# AMC.net
KiCad netlist of a schematic drawn in Altium Designer
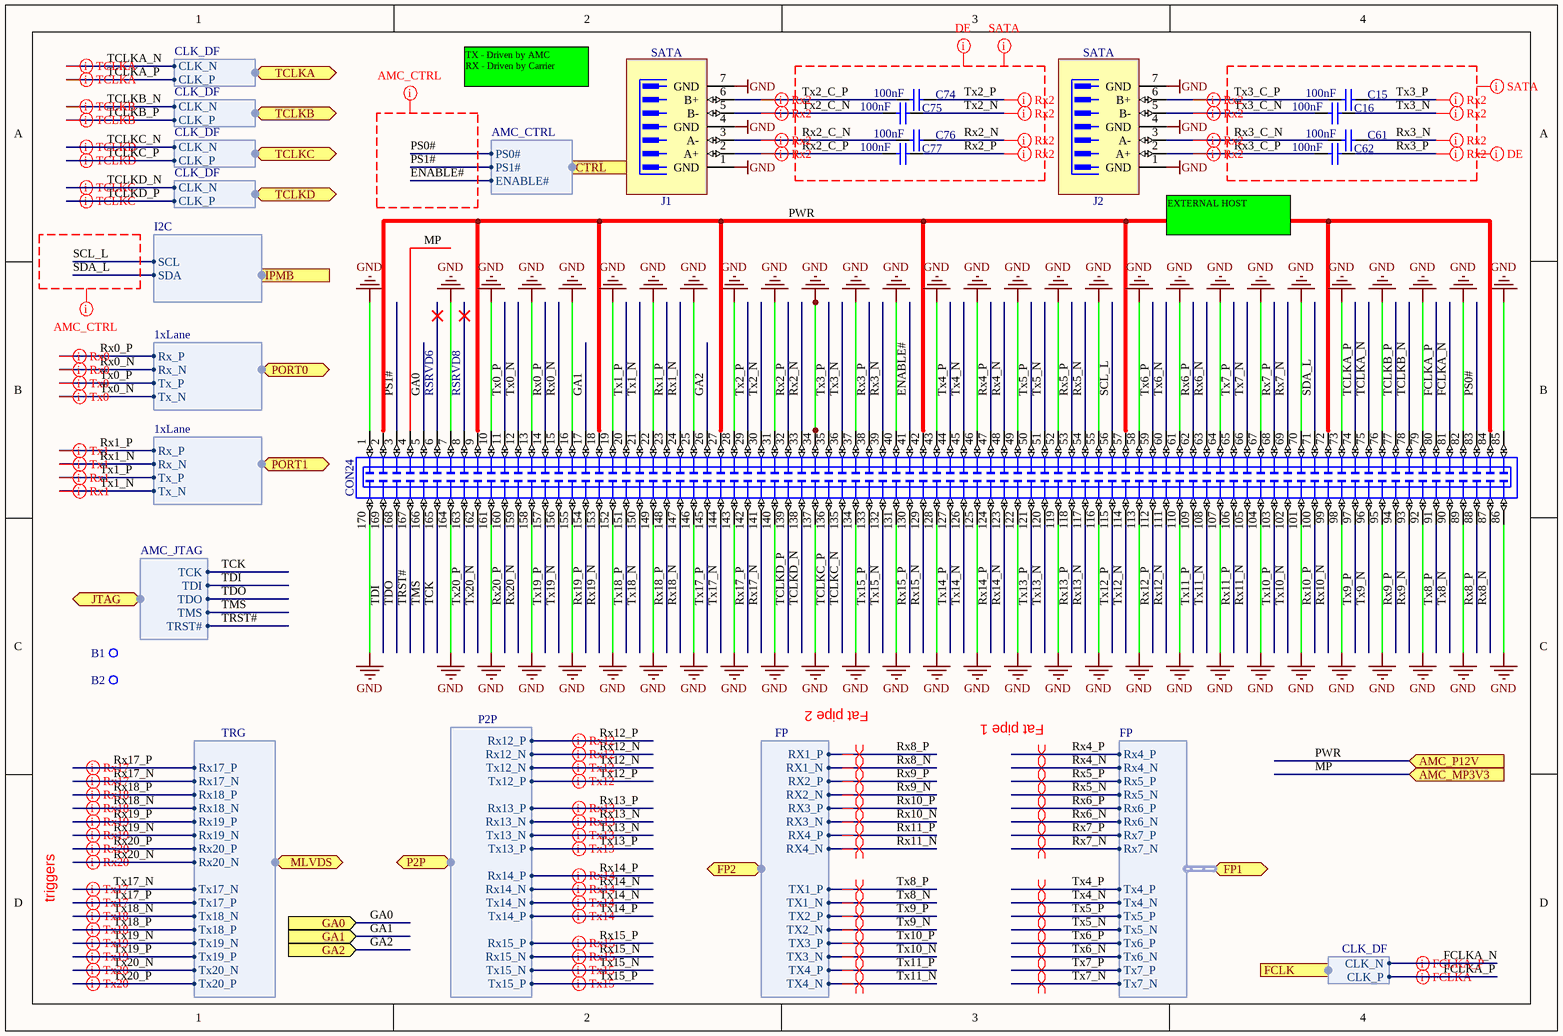
[diagram p0: AMC.SchDoc]

(export (version "E")
  (design (tool "Eeschema 10.0.6"))
  (components
    (comp (ref "B1")
      (value "Plated Hole")
      (footprint "MTG320_550")
      (description "Single Terminal Socket")
      (fields (field (name "PART NUMBER") "PLATED_HOLE3.2_PAD5.5") (field (name "AUTHOR") "CERN DEM JMW"))
      (libsource (lib "Eletro-mechanical") (part "Single Terminal Socket"))
    )
    (comp (ref "B2")
      (value "Plated Hole")
      (footprint "MTG320_550")
      (description "Single Terminal Socket")
      (fields (field (name "PART NUMBER") "PLATED_HOLE3.2_PAD5.5") (field (name "AUTHOR") "CERN DEM JMW"))
      (libsource (lib "Eletro-mechanical") (part "Single Terminal Socket"))
    )
    (comp (ref "C15")
      (value "100nF")
      (footprint "CAPC0603X33N")
      (description "Non-polarised capacitor")
      (fields
        (field (name "PART NUMBER") "CC0201_100NF_6.3V_10%_X5R")
        (field (name "VOLTAGE") "6.3V")
        (field (name "AUTHOR") "CERN DEM JLC")
      )
      (libsource (lib "Capacitors") (part "Capacitor - non polarized"))
    )
    (comp (ref "C16")
      (value "100nF")
      (footprint "CAPC0603X33N")
      (description "Non-polarised capacitor")
      (fields
        (field (name "PART NUMBER") "CC0201_100NF_6.3V_10%_X5R")
        (field (name "VOLTAGE") "6.3V")
        (field (name "AUTHOR") "CERN DEM JLC")
      )
      (libsource (lib "Capacitors") (part "Capacitor - non polarized"))
    )
    (comp (ref "C61")
      (value "100nF")
      (footprint "CAPC0603X33N")
      (description "Non-polarised capacitor")
      (fields
        (field (name "PART NUMBER") "CC0201_100NF_6.3V_10%_X5R")
        (field (name "VOLTAGE") "6.3V")
        (field (name "AUTHOR") "CERN DEM JLC")
      )
      (libsource (lib "Capacitors") (part "Capacitor - non polarized"))
    )
    (comp (ref "C62")
      (value "100nF")
      (footprint "CAPC0603X33N")
      (description "Non-polarised capacitor")
      (fields
        (field (name "PART NUMBER") "CC0201_100NF_6.3V_10%_X5R")
        (field (name "VOLTAGE") "6.3V")
        (field (name "AUTHOR") "CERN DEM JLC")
      )
      (libsource (lib "Capacitors") (part "Capacitor - non polarized"))
    )
    (comp (ref "C74")
      (value "100nF")
      (footprint "CAPC0603X33N")
      (description "Non-polarised capacitor")
      (fields
        (field (name "PART NUMBER") "CC0201_100NF_6.3V_10%_X5R")
        (field (name "VOLTAGE") "6.3V")
        (field (name "AUTHOR") "CERN DEM JLC")
      )
      (libsource (lib "Capacitors") (part "Capacitor - non polarized"))
    )
    (comp (ref "C75")
      (value "100nF")
      (footprint "CAPC0603X33N")
      (description "Non-polarised capacitor")
      (fields
        (field (name "PART NUMBER") "CC0201_100NF_6.3V_10%_X5R")
        (field (name "VOLTAGE") "6.3V")
        (field (name "AUTHOR") "CERN DEM JLC")
      )
      (libsource (lib "Capacitors") (part "Capacitor - non polarized"))
    )
    (comp (ref "C76")
      (value "100nF")
      (footprint "CAPC0603X33N")
      (description "Non-polarised capacitor")
      (fields
        (field (name "PART NUMBER") "CC0201_100NF_6.3V_10%_X5R")
        (field (name "VOLTAGE") "6.3V")
        (field (name "AUTHOR") "CERN DEM JLC")
      )
      (libsource (lib "Capacitors") (part "Capacitor - non polarized"))
    )
    (comp (ref "C77")
      (value "100nF")
      (footprint "CAPC0603X33N")
      (description "Non-polarised capacitor")
      (fields
        (field (name "PART NUMBER") "CC0201_100NF_6.3V_10%_X5R")
        (field (name "VOLTAGE") "6.3V")
        (field (name "AUTHOR") "CERN DEM JLC")
      )
      (libsource (lib "Capacitors") (part "Capacitor - non polarized"))
    )
    (comp (ref "CON24")
      (value "SAMTEC_MTCA-085-02-S-DV-SMT-K-TR")
      (footprint "SAMTEC_MTCA-085-02-S-DV-SMT-K-TR")
      (description "170 Poles,  Micro TCA (Telecom Computing Architecture) Edge Card Socket")
      (fields
        (field (name "MANUFACTURER") "SAMTEC")
        (field (name "MANUFACTURER PART NUMBER") "MTCA-085-02-S-DV-SMT-K-TR")
        (field (name "AUTHOR") "CERN DEM JLC")
      )
      (libsource (lib "Connectors") (part "Micro TCA Female 170"))
    )
    (comp (ref "J1")
      (value "SATA")
      (footprint "MOLEX_67800-5005")
      (description "7 Pin SATA Receptacle")
      (fields
        (field (name "PART NUMBER") "MOLEX_67800-5005")
        (field (name "MANUFACTURER") "MOLEX")
        (field (name "AUTHOR") "CERN DEM MR")
      )
      (libsource (lib "Connectors") (part "Connector SATA 7 Male"))
    )
    (comp (ref "J2")
      (value "SATA")
      (footprint "MOLEX_67800-5005")
      (description "7 Pin SATA Receptacle")
      (fields
        (field (name "PART NUMBER") "MOLEX_67800-5005")
        (field (name "MANUFACTURER") "MOLEX")
        (field (name "AUTHOR") "CERN DEM MR")
      )
      (libsource (lib "Connectors") (part "Connector SATA 7 Male"))
    )
  )
  (nets
    (net (code "9") (name "/ENABLE#") (class "Default")
      (node (ref "CON24") (pin "41") (pinfunction "41_41") (pintype "bidirectional"))
    )
    (net (code "10") (name "/FCLKA_N") (class "Default")
      (node (ref "CON24") (pin "81") (pinfunction "81_81") (pintype "bidirectional"))
    )
    (net (code "11") (name "/FCLKA_P") (class "Default")
      (node (ref "CON24") (pin "80") (pinfunction "80_80") (pintype "bidirectional"))
    )
    (net (code "12") (name "/GA0") (class "Default")
      (node (ref "CON24") (pin "5") (pinfunction "5_5") (pintype "bidirectional"))
    )
    (net (code "13") (name "/GA1") (class "Default")
      (node (ref "CON24") (pin "17") (pinfunction "17_17") (pintype "bidirectional"))
    )
    (net (code "14") (name "/GA2") (class "Default")
      (node (ref "CON24") (pin "26") (pinfunction "26_26") (pintype "bidirectional"))
    )
    (net (code "15") (name "/MP") (class "Default")
      (node (ref "CON24") (pin "4") (pinfunction "4_4") (pintype "bidirectional"))
    )
    (net (code "16") (name "/PS0#") (class "Default")
      (node (ref "CON24") (pin "83") (pinfunction "83_83") (pintype "bidirectional"))
    )
    (net (code "17") (name "/PS1#") (class "Default")
      (node (ref "CON24") (pin "3") (pinfunction "3_3") (pintype "bidirectional"))
    )
    (net (code "18") (name "/PWR") (class "Default")
      (node (ref "CON24") (pin "18") (pinfunction "18_18") (pintype "bidirectional"))
      (node (ref "CON24") (pin "2") (pinfunction "2_2") (pintype "bidirectional"))
      (node (ref "CON24") (pin "27") (pinfunction "27_27") (pintype "bidirectional"))
      (node (ref "CON24") (pin "42") (pinfunction "42_42") (pintype "bidirectional"))
      (node (ref "CON24") (pin "57") (pinfunction "57_57") (pintype "bidirectional"))
      (node (ref "CON24") (pin "72") (pinfunction "72_72") (pintype "bidirectional"))
      (node (ref "CON24") (pin "84") (pinfunction "84_84") (pintype "bidirectional"))
      (node (ref "CON24") (pin "9") (pinfunction "9_9") (pintype "bidirectional"))
    )
    (net (code "19") (name "/Rx0_N") (class "Default")
      (node (ref "CON24") (pin "15") (pinfunction "15_15") (pintype "bidirectional"))
    )
    (net (code "20") (name "/Rx0_P") (class "Default")
      (node (ref "CON24") (pin "14") (pinfunction "14_14") (pintype "bidirectional"))
    )
    (net (code "21") (name "/Rx1_N") (class "Default")
      (node (ref "CON24") (pin "24") (pinfunction "24_24") (pintype "bidirectional"))
    )
    (net (code "22") (name "/Rx1_P") (class "Default")
      (node (ref "CON24") (pin "23") (pinfunction "23_23") (pintype "bidirectional"))
    )
    (net (code "23") (name "/Rx2_C_N") (class "Default")
      (node (ref "C76") (pin "1") (pinfunction "1_1") (pintype "passive"))
      (node (ref "J1") (pin "3") (pinfunction "A-_3") (pintype "bidirectional"))
    )
    (net (code "24") (name "/Rx2_C_P") (class "Default")
      (node (ref "C77") (pin "1") (pinfunction "1_1") (pintype "passive"))
      (node (ref "J1") (pin "2") (pinfunction "A+_2") (pintype "bidirectional"))
    )
    (net (code "25") (name "/Rx2_N") (class "Default")
      (node (ref "C76") (pin "2") (pinfunction "2_2") (pintype "passive"))
      (node (ref "CON24") (pin "33") (pinfunction "33_33") (pintype "bidirectional"))
    )
    (net (code "26") (name "/Rx2_P") (class "Default")
      (node (ref "C77") (pin "2") (pinfunction "2_2") (pintype "passive"))
      (node (ref "CON24") (pin "32") (pinfunction "32_32") (pintype "bidirectional"))
    )
    (net (code "27") (name "/Rx3_C_N") (class "Default")
      (node (ref "C61") (pin "1") (pinfunction "1_1") (pintype "passive"))
      (node (ref "J2") (pin "3") (pinfunction "A-_3") (pintype "bidirectional"))
    )
    (net (code "28") (name "/Rx3_C_P") (class "Default")
      (node (ref "C62") (pin "1") (pinfunction "1_1") (pintype "passive"))
      (node (ref "J2") (pin "2") (pinfunction "A+_2") (pintype "bidirectional"))
    )
    (net (code "29") (name "/Rx3_N") (class "Default")
      (node (ref "C61") (pin "2") (pinfunction "2_2") (pintype "passive"))
      (node (ref "CON24") (pin "39") (pinfunction "39_39") (pintype "bidirectional"))
    )
    (net (code "30") (name "/Rx3_P") (class "Default")
      (node (ref "C62") (pin "2") (pinfunction "2_2") (pintype "passive"))
      (node (ref "CON24") (pin "38") (pinfunction "38_38") (pintype "bidirectional"))
    )
    (net (code "31") (name "/Rx4_N") (class "Default")
      (node (ref "CON24") (pin "48") (pinfunction "48_48") (pintype "bidirectional"))
    )
    (net (code "32") (name "/Rx4_P") (class "Default")
      (node (ref "CON24") (pin "47") (pinfunction "47_47") (pintype "bidirectional"))
    )
    (net (code "33") (name "/Rx5_N") (class "Default")
      (node (ref "CON24") (pin "54") (pinfunction "54_54") (pintype "bidirectional"))
    )
    (net (code "34") (name "/Rx5_P") (class "Default")
      (node (ref "CON24") (pin "53") (pinfunction "53_53") (pintype "bidirectional"))
    )
    (net (code "35") (name "/Rx6_N") (class "Default")
      (node (ref "CON24") (pin "63") (pinfunction "63_63") (pintype "bidirectional"))
    )
    (net (code "36") (name "/Rx6_P") (class "Default")
      (node (ref "CON24") (pin "62") (pinfunction "62_62") (pintype "bidirectional"))
    )
    (net (code "37") (name "/Rx7_N") (class "Default")
      (node (ref "CON24") (pin "69") (pinfunction "69_69") (pintype "bidirectional"))
    )
    (net (code "38") (name "/Rx7_P") (class "Default")
      (node (ref "CON24") (pin "68") (pinfunction "68_68") (pintype "bidirectional"))
    )
    (net (code "39") (name "/Rx8_N") (class "Default")
      (node (ref "CON24") (pin "87") (pinfunction "87_87") (pintype "bidirectional"))
    )
    (net (code "40") (name "/Rx8_P") (class "Default")
      (node (ref "CON24") (pin "88") (pinfunction "88_88") (pintype "bidirectional"))
    )
    (net (code "41") (name "/Rx9_N") (class "Default")
      (node (ref "CON24") (pin "93") (pinfunction "93_93") (pintype "bidirectional"))
    )
    (net (code "42") (name "/Rx9_P") (class "Default")
      (node (ref "CON24") (pin "94") (pinfunction "94_94") (pintype "bidirectional"))
    )
    (net (code "43") (name "/Rx10_N") (class "Default")
      (node (ref "CON24") (pin "99") (pinfunction "99_99") (pintype "bidirectional"))
    )
    (net (code "44") (name "/Rx10_P") (class "Default")
      (node (ref "CON24") (pin "100") (pinfunction "100_100") (pintype "bidirectional"))
    )
    (net (code "45") (name "/Rx11_N") (class "Default")
      (node (ref "CON24") (pin "105") (pinfunction "105_105") (pintype "bidirectional"))
    )
    (net (code "46") (name "/Rx11_P") (class "Default")
      (node (ref "CON24") (pin "106") (pinfunction "106_106") (pintype "bidirectional"))
    )
    (net (code "47") (name "/Rx12_N") (class "Default")
      (node (ref "CON24") (pin "111") (pinfunction "111_111") (pintype "bidirectional"))
    )
    (net (code "48") (name "/Rx12_P") (class "Default")
      (node (ref "CON24") (pin "112") (pinfunction "112_112") (pintype "bidirectional"))
    )
    (net (code "49") (name "/Rx13_N") (class "Default")
      (node (ref "CON24") (pin "117") (pinfunction "117_117") (pintype "bidirectional"))
    )
    (net (code "50") (name "/Rx13_P") (class "Default")
      (node (ref "CON24") (pin "118") (pinfunction "118_118") (pintype "bidirectional"))
    )
    (net (code "51") (name "/Rx14_N") (class "Default")
      (node (ref "CON24") (pin "123") (pinfunction "123_123") (pintype "bidirectional"))
    )
    (net (code "52") (name "/Rx14_P") (class "Default")
      (node (ref "CON24") (pin "124") (pinfunction "124_124") (pintype "bidirectional"))
    )
    (net (code "53") (name "/Rx15_N") (class "Default")
      (node (ref "CON24") (pin "129") (pinfunction "129_129") (pintype "bidirectional"))
    )
    (net (code "54") (name "/Rx15_P") (class "Default")
      (node (ref "CON24") (pin "130") (pinfunction "130_130") (pintype "bidirectional"))
    )
    (net (code "55") (name "/Rx17_N") (class "Default")
      (node (ref "CON24") (pin "141") (pinfunction "141_141") (pintype "bidirectional"))
    )
    (net (code "56") (name "/Rx17_P") (class "Default")
      (node (ref "CON24") (pin "142") (pinfunction "142_142") (pintype "bidirectional"))
    )
    (net (code "57") (name "/Rx18_N") (class "Default")
      (node (ref "CON24") (pin "147") (pinfunction "147_147") (pintype "bidirectional"))
    )
    (net (code "58") (name "/Rx18_P") (class "Default")
      (node (ref "CON24") (pin "148") (pinfunction "148_148") (pintype "bidirectional"))
    )
    (net (code "59") (name "/Rx19_N") (class "Default")
      (node (ref "CON24") (pin "153") (pinfunction "153_153") (pintype "bidirectional"))
    )
    (net (code "60") (name "/Rx19_P") (class "Default")
      (node (ref "CON24") (pin "154") (pinfunction "154_154") (pintype "bidirectional"))
    )
    (net (code "61") (name "/Rx20_N") (class "Default")
      (node (ref "CON24") (pin "159") (pinfunction "159_159") (pintype "bidirectional"))
    )
    (net (code "62") (name "/Rx20_P") (class "Default")
      (node (ref "CON24") (pin "160") (pinfunction "160_160") (pintype "bidirectional"))
    )
    (net (code "63") (name "/SCL_L") (class "Default")
      (node (ref "CON24") (pin "56") (pinfunction "56_56") (pintype "bidirectional"))
    )
    (net (code "64") (name "/SDA_L") (class "Default")
      (node (ref "CON24") (pin "71") (pinfunction "71_71") (pintype "bidirectional"))
    )
    (net (code "65") (name "/TCK") (class "Default")
      (node (ref "CON24") (pin "165") (pinfunction "165_165") (pintype "bidirectional"))
    )
    (net (code "66") (name "/TCLKA_N") (class "Default")
      (node (ref "CON24") (pin "75") (pinfunction "75_75") (pintype "bidirectional"))
    )
    (net (code "67") (name "/TCLKA_P") (class "Default")
      (node (ref "CON24") (pin "74") (pinfunction "74_74") (pintype "bidirectional"))
    )
    (net (code "68") (name "/TCLKB_N") (class "Default")
      (node (ref "CON24") (pin "78") (pinfunction "78_78") (pintype "bidirectional"))
    )
    (net (code "69") (name "/TCLKB_P") (class "Default")
      (node (ref "CON24") (pin "77") (pinfunction "77_77") (pintype "bidirectional"))
    )
    (net (code "70") (name "/TCLKC_N") (class "Default")
      (node (ref "CON24") (pin "135") (pinfunction "135_135") (pintype "bidirectional"))
    )
    (net (code "71") (name "/TCLKC_P") (class "Default")
      (node (ref "CON24") (pin "136") (pinfunction "136_136") (pintype "bidirectional"))
    )
    (net (code "72") (name "/TCLKD_N") (class "Default")
      (node (ref "CON24") (pin "138") (pinfunction "138_138") (pintype "bidirectional"))
    )
    (net (code "73") (name "/TCLKD_P") (class "Default")
      (node (ref "CON24") (pin "139") (pinfunction "139_139") (pintype "bidirectional"))
    )
    (net (code "74") (name "/TDI") (class "Default")
      (node (ref "CON24") (pin "169") (pinfunction "169_169") (pintype "bidirectional"))
    )
    (net (code "75") (name "/TDO") (class "Default")
      (node (ref "CON24") (pin "168") (pinfunction "168_168") (pintype "bidirectional"))
    )
    (net (code "76") (name "/TMS") (class "Default")
      (node (ref "CON24") (pin "166") (pinfunction "166_166") (pintype "bidirectional"))
    )
    (net (code "77") (name "/TRST#") (class "Default")
      (node (ref "CON24") (pin "167") (pinfunction "167_167") (pintype "bidirectional"))
    )
    (net (code "78") (name "/Tx0_N") (class "Default")
      (node (ref "CON24") (pin "12") (pinfunction "12_12") (pintype "bidirectional"))
    )
    (net (code "79") (name "/Tx0_P") (class "Default")
      (node (ref "CON24") (pin "11") (pinfunction "11_11") (pintype "bidirectional"))
    )
    (net (code "80") (name "/Tx1_N") (class "Default")
      (node (ref "CON24") (pin "21") (pinfunction "21_21") (pintype "bidirectional"))
    )
    (net (code "81") (name "/Tx1_P") (class "Default")
      (node (ref "CON24") (pin "20") (pinfunction "20_20") (pintype "bidirectional"))
    )
    (net (code "82") (name "/Tx2_C_N") (class "Default")
      (node (ref "C75") (pin "1") (pinfunction "1_1") (pintype "passive"))
      (node (ref "J1") (pin "5") (pinfunction "B-_5") (pintype "bidirectional"))
    )
    (net (code "83") (name "/Tx2_C_P") (class "Default")
      (node (ref "C74") (pin "1") (pinfunction "1_1") (pintype "passive"))
      (node (ref "J1") (pin "6") (pinfunction "B+_6") (pintype "bidirectional"))
    )
    (net (code "84") (name "/Tx2_N") (class "Default")
      (node (ref "C75") (pin "2") (pinfunction "2_2") (pintype "passive"))
      (node (ref "CON24") (pin "30") (pinfunction "30_30") (pintype "bidirectional"))
    )
    (net (code "85") (name "/Tx2_P") (class "Default")
      (node (ref "C74") (pin "2") (pinfunction "2_2") (pintype "passive"))
      (node (ref "CON24") (pin "29") (pinfunction "29_29") (pintype "bidirectional"))
    )
    (net (code "86") (name "/Tx3_C_N") (class "Default")
      (node (ref "C16") (pin "1") (pinfunction "1_1") (pintype "passive"))
      (node (ref "J2") (pin "5") (pinfunction "B-_5") (pintype "bidirectional"))
    )
    (net (code "87") (name "/Tx3_C_P") (class "Default")
      (node (ref "C15") (pin "1") (pinfunction "1_1") (pintype "passive"))
      (node (ref "J2") (pin "6") (pinfunction "B+_6") (pintype "bidirectional"))
    )
    (net (code "88") (name "/Tx3_N") (class "Default")
      (node (ref "C16") (pin "2") (pinfunction "2_2") (pintype "passive"))
      (node (ref "CON24") (pin "36") (pinfunction "36_36") (pintype "bidirectional"))
    )
    (net (code "89") (name "/Tx3_P") (class "Default")
      (node (ref "C15") (pin "2") (pinfunction "2_2") (pintype "passive"))
      (node (ref "CON24") (pin "35") (pinfunction "35_35") (pintype "bidirectional"))
    )
    (net (code "90") (name "/Tx4_N") (class "Default")
      (node (ref "CON24") (pin "45") (pinfunction "45_45") (pintype "bidirectional"))
    )
    (net (code "91") (name "/Tx4_P") (class "Default")
      (node (ref "CON24") (pin "44") (pinfunction "44_44") (pintype "bidirectional"))
    )
    (net (code "92") (name "/Tx5_N") (class "Default")
      (node (ref "CON24") (pin "51") (pinfunction "51_51") (pintype "bidirectional"))
    )
    (net (code "93") (name "/Tx5_P") (class "Default")
      (node (ref "CON24") (pin "50") (pinfunction "50_50") (pintype "bidirectional"))
    )
    (net (code "94") (name "/Tx6_N") (class "Default")
      (node (ref "CON24") (pin "60") (pinfunction "60_60") (pintype "bidirectional"))
    )
    (net (code "95") (name "/Tx6_P") (class "Default")
      (node (ref "CON24") (pin "59") (pinfunction "59_59") (pintype "bidirectional"))
    )
    (net (code "96") (name "/Tx7_N") (class "Default")
      (node (ref "CON24") (pin "66") (pinfunction "66_66") (pintype "bidirectional"))
    )
    (net (code "97") (name "/Tx7_P") (class "Default")
      (node (ref "CON24") (pin "65") (pinfunction "65_65") (pintype "bidirectional"))
    )
    (net (code "98") (name "/Tx8_N") (class "Default")
      (node (ref "CON24") (pin "90") (pinfunction "90_90") (pintype "bidirectional"))
    )
    (net (code "99") (name "/Tx8_P") (class "Default")
      (node (ref "CON24") (pin "91") (pinfunction "91_91") (pintype "bidirectional"))
    )
    (net (code "100") (name "/Tx9_N") (class "Default")
      (node (ref "CON24") (pin "96") (pinfunction "96_96") (pintype "bidirectional"))
    )
    (net (code "101") (name "/Tx9_P") (class "Default")
      (node (ref "CON24") (pin "97") (pinfunction "97_97") (pintype "bidirectional"))
    )
    (net (code "102") (name "/Tx10_N") (class "Default")
      (node (ref "CON24") (pin "102") (pinfunction "102_102") (pintype "bidirectional"))
    )
    (net (code "103") (name "/Tx10_P") (class "Default")
      (node (ref "CON24") (pin "103") (pinfunction "103_103") (pintype "bidirectional"))
    )
    (net (code "104") (name "/Tx11_N") (class "Default")
      (node (ref "CON24") (pin "108") (pinfunction "108_108") (pintype "bidirectional"))
    )
    (net (code "105") (name "/Tx11_P") (class "Default")
      (node (ref "CON24") (pin "109") (pinfunction "109_109") (pintype "bidirectional"))
    )
    (net (code "106") (name "/Tx12_N") (class "Default")
      (node (ref "CON24") (pin "114") (pinfunction "114_114") (pintype "bidirectional"))
    )
    (net (code "107") (name "/Tx12_P") (class "Default")
      (node (ref "CON24") (pin "115") (pinfunction "115_115") (pintype "bidirectional"))
    )
    (net (code "108") (name "/Tx13_N") (class "Default")
      (node (ref "CON24") (pin "120") (pinfunction "120_120") (pintype "bidirectional"))
    )
    (net (code "109") (name "/Tx13_P") (class "Default")
      (node (ref "CON24") (pin "121") (pinfunction "121_121") (pintype "bidirectional"))
    )
    (net (code "110") (name "/Tx14_N") (class "Default")
      (node (ref "CON24") (pin "126") (pinfunction "126_126") (pintype "bidirectional"))
    )
    (net (code "111") (name "/Tx14_P") (class "Default")
      (node (ref "CON24") (pin "127") (pinfunction "127_127") (pintype "bidirectional"))
    )
    (net (code "112") (name "/Tx15_N") (class "Default")
      (node (ref "CON24") (pin "132") (pinfunction "132_132") (pintype "bidirectional"))
    )
    (net (code "113") (name "/Tx15_P") (class "Default")
      (node (ref "CON24") (pin "133") (pinfunction "133_133") (pintype "bidirectional"))
    )
    (net (code "114") (name "/Tx17_N") (class "Default")
      (node (ref "CON24") (pin "144") (pinfunction "144_144") (pintype "bidirectional"))
    )
    (net (code "115") (name "/Tx17_P") (class "Default")
      (node (ref "CON24") (pin "145") (pinfunction "145_145") (pintype "bidirectional"))
    )
    (net (code "116") (name "/Tx18_N") (class "Default")
      (node (ref "CON24") (pin "150") (pinfunction "150_150") (pintype "bidirectional"))
    )
    (net (code "117") (name "/Tx18_P") (class "Default")
      (node (ref "CON24") (pin "151") (pinfunction "151_151") (pintype "bidirectional"))
    )
    (net (code "118") (name "/Tx19_N") (class "Default")
      (node (ref "CON24") (pin "156") (pinfunction "156_156") (pintype "bidirectional"))
    )
    (net (code "119") (name "/Tx19_P") (class "Default")
      (node (ref "CON24") (pin "157") (pinfunction "157_157") (pintype "bidirectional"))
    )
    (net (code "120") (name "/Tx20_N") (class "Default")
      (node (ref "CON24") (pin "162") (pinfunction "162_162") (pintype "bidirectional"))
    )
    (net (code "121") (name "/Tx20_P") (class "Default")
      (node (ref "CON24") (pin "163") (pinfunction "163_163") (pintype "bidirectional"))
    )
    (net (code "130") (name "GND") (class "Default")
      (node (ref "CON24") (pin "1") (pinfunction "1_1") (pintype "bidirectional"))
      (node (ref "CON24") (pin "10") (pinfunction "10_10") (pintype "bidirectional"))
      (node (ref "CON24") (pin "101") (pinfunction "101_101") (pintype "bidirectional"))
      (node (ref "CON24") (pin "104") (pinfunction "104_104") (pintype "bidirectional"))
      (node (ref "CON24") (pin "107") (pinfunction "107_107") (pintype "bidirectional"))
      (node (ref "CON24") (pin "110") (pinfunction "110_110") (pintype "bidirectional"))
      (node (ref "CON24") (pin "113") (pinfunction "113_113") (pintype "bidirectional"))
      (node (ref "CON24") (pin "116") (pinfunction "116_116") (pintype "bidirectional"))
      (node (ref "CON24") (pin "119") (pinfunction "119_119") (pintype "bidirectional"))
      (node (ref "CON24") (pin "122") (pinfunction "122_122") (pintype "bidirectional"))
      (node (ref "CON24") (pin "125") (pinfunction "125_125") (pintype "bidirectional"))
      (node (ref "CON24") (pin "128") (pinfunction "128_128") (pintype "bidirectional"))
      (node (ref "CON24") (pin "13") (pinfunction "13_13") (pintype "bidirectional"))
      (node (ref "CON24") (pin "131") (pinfunction "131_131") (pintype "bidirectional"))
      (node (ref "CON24") (pin "134") (pinfunction "134_134") (pintype "bidirectional"))
      (node (ref "CON24") (pin "137") (pinfunction "137_137") (pintype "bidirectional"))
      (node (ref "CON24") (pin "140") (pinfunction "140_140") (pintype "bidirectional"))
      (node (ref "CON24") (pin "143") (pinfunction "143_143") (pintype "bidirectional"))
      (node (ref "CON24") (pin "146") (pinfunction "146_146") (pintype "bidirectional"))
      (node (ref "CON24") (pin "149") (pinfunction "149_149") (pintype "bidirectional"))
      (node (ref "CON24") (pin "152") (pinfunction "152_152") (pintype "bidirectional"))
      (node (ref "CON24") (pin "155") (pinfunction "155_155") (pintype "bidirectional"))
      (node (ref "CON24") (pin "158") (pinfunction "158_158") (pintype "bidirectional"))
      (node (ref "CON24") (pin "16") (pinfunction "16_16") (pintype "bidirectional"))
      (node (ref "CON24") (pin "161") (pinfunction "161_161") (pintype "bidirectional"))
      (node (ref "CON24") (pin "164") (pinfunction "164_164") (pintype "bidirectional"))
      (node (ref "CON24") (pin "170") (pinfunction "170_170") (pintype "bidirectional"))
      (node (ref "CON24") (pin "19") (pinfunction "19_19") (pintype "bidirectional"))
      (node (ref "CON24") (pin "22") (pinfunction "22_22") (pintype "bidirectional"))
      (node (ref "CON24") (pin "25") (pinfunction "25_25") (pintype "bidirectional"))
      (node (ref "CON24") (pin "28") (pinfunction "28_28") (pintype "bidirectional"))
      (node (ref "CON24") (pin "31") (pinfunction "31_31") (pintype "bidirectional"))
      (node (ref "CON24") (pin "34") (pinfunction "34_34") (pintype "bidirectional"))
      (node (ref "CON24") (pin "37") (pinfunction "37_37") (pintype "bidirectional"))
      (node (ref "CON24") (pin "40") (pinfunction "40_40") (pintype "bidirectional"))
      (node (ref "CON24") (pin "43") (pinfunction "43_43") (pintype "bidirectional"))
      (node (ref "CON24") (pin "46") (pinfunction "46_46") (pintype "bidirectional"))
      (node (ref "CON24") (pin "49") (pinfunction "49_49") (pintype "bidirectional"))
      (node (ref "CON24") (pin "52") (pinfunction "52_52") (pintype "bidirectional"))
      (node (ref "CON24") (pin "55") (pinfunction "55_55") (pintype "bidirectional"))
      (node (ref "CON24") (pin "58") (pinfunction "58_58") (pintype "bidirectional"))
      (node (ref "CON24") (pin "61") (pinfunction "61_61") (pintype "bidirectional"))
      (node (ref "CON24") (pin "64") (pinfunction "64_64") (pintype "bidirectional"))
      (node (ref "CON24") (pin "67") (pinfunction "67_67") (pintype "bidirectional"))
      (node (ref "CON24") (pin "7") (pinfunction "7_7") (pintype "bidirectional"))
      (node (ref "CON24") (pin "70") (pinfunction "70_70") (pintype "bidirectional"))
      (node (ref "CON24") (pin "73") (pinfunction "73_73") (pintype "bidirectional"))
      (node (ref "CON24") (pin "76") (pinfunction "76_76") (pintype "bidirectional"))
      (node (ref "CON24") (pin "79") (pinfunction "79_79") (pintype "bidirectional"))
      (node (ref "CON24") (pin "82") (pinfunction "82_82") (pintype "bidirectional"))
      (node (ref "CON24") (pin "85") (pinfunction "85_85") (pintype "bidirectional"))
      (node (ref "CON24") (pin "86") (pinfunction "86_86") (pintype "bidirectional"))
      (node (ref "CON24") (pin "89") (pinfunction "89_89") (pintype "bidirectional"))
      (node (ref "CON24") (pin "92") (pinfunction "92_92") (pintype "bidirectional"))
      (node (ref "CON24") (pin "95") (pinfunction "95_95") (pintype "bidirectional"))
      (node (ref "CON24") (pin "98") (pinfunction "98_98") (pintype "bidirectional"))
      (node (ref "J1") (pin "1") (pinfunction "GND_1") (pintype "power_in"))
      (node (ref "J1") (pin "4") (pinfunction "GND_4") (pintype "power_in"))
      (node (ref "J1") (pin "7") (pinfunction "GND_7") (pintype "power_in"))
      (node (ref "J2") (pin "1") (pinfunction "GND_1") (pintype "power_in"))
      (node (ref "J2") (pin "4") (pinfunction "GND_4") (pintype "power_in"))
      (node (ref "J2") (pin "7") (pinfunction "GND_7") (pintype "power_in"))
    )
    (net (code "131") (name "unconnected-(B1-Pad1)") (class "Default")
      (node (ref "B1") (pin "1") (pinfunction "1_1") (pintype "bidirectional"))
    )
    (net (code "132") (name "unconnected-(B2-Pad1)") (class "Default")
      (node (ref "B2") (pin "1") (pinfunction "1_1") (pintype "bidirectional"))
    )
    (net (code "133") (name "unconnected-(CON24-Pad6)") (class "Default")
      (node (ref "CON24") (pin "6") (pinfunction "6_6") (pintype "bidirectional"))
    )
    (net (code "134") (name "unconnected-(CON24-Pad8)") (class "Default")
      (node (ref "CON24") (pin "8") (pinfunction "8_8") (pintype "bidirectional"))
    )
  )
)
